# 00_PINOUT.net
KiCad netlist of a schematic drawn in Altium Designer
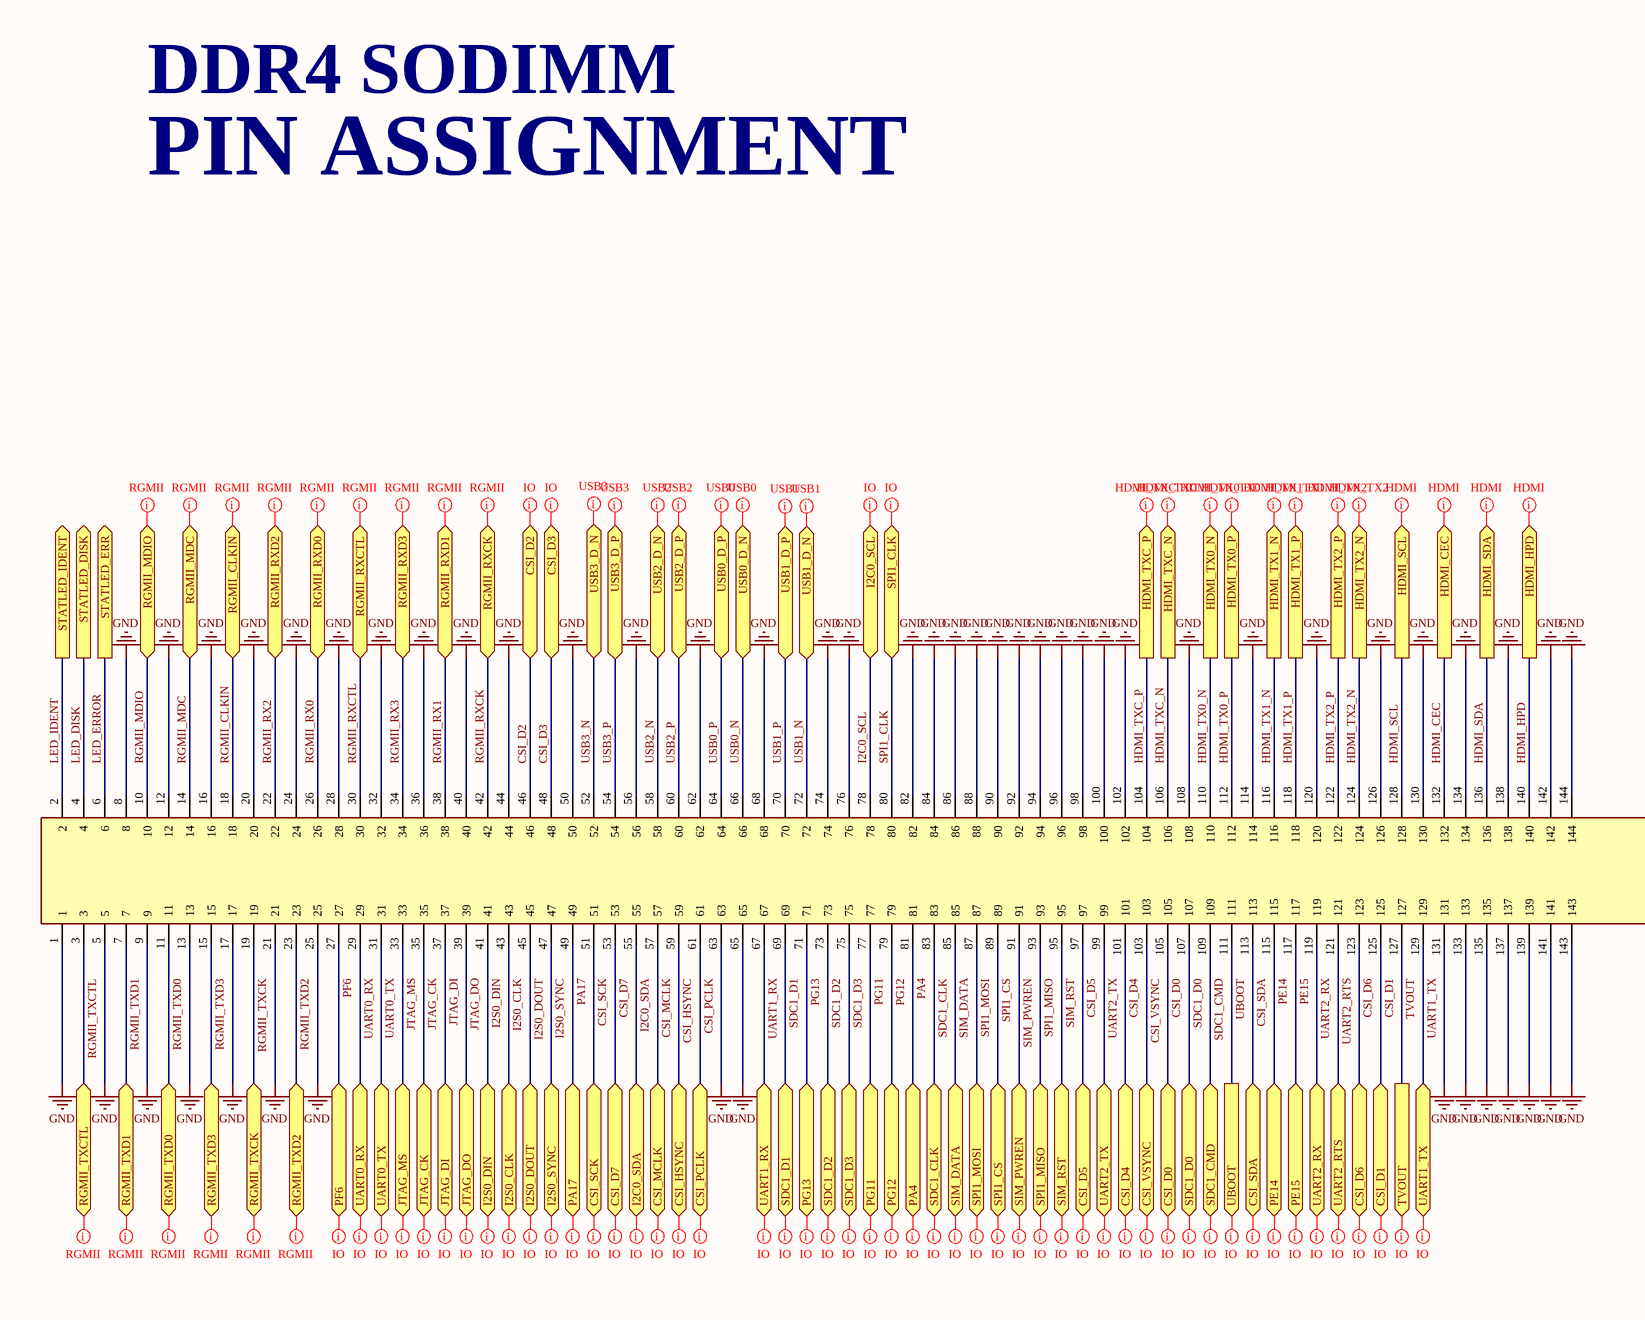
[diagram p0: 00_PINOUT.SchDoc, left]
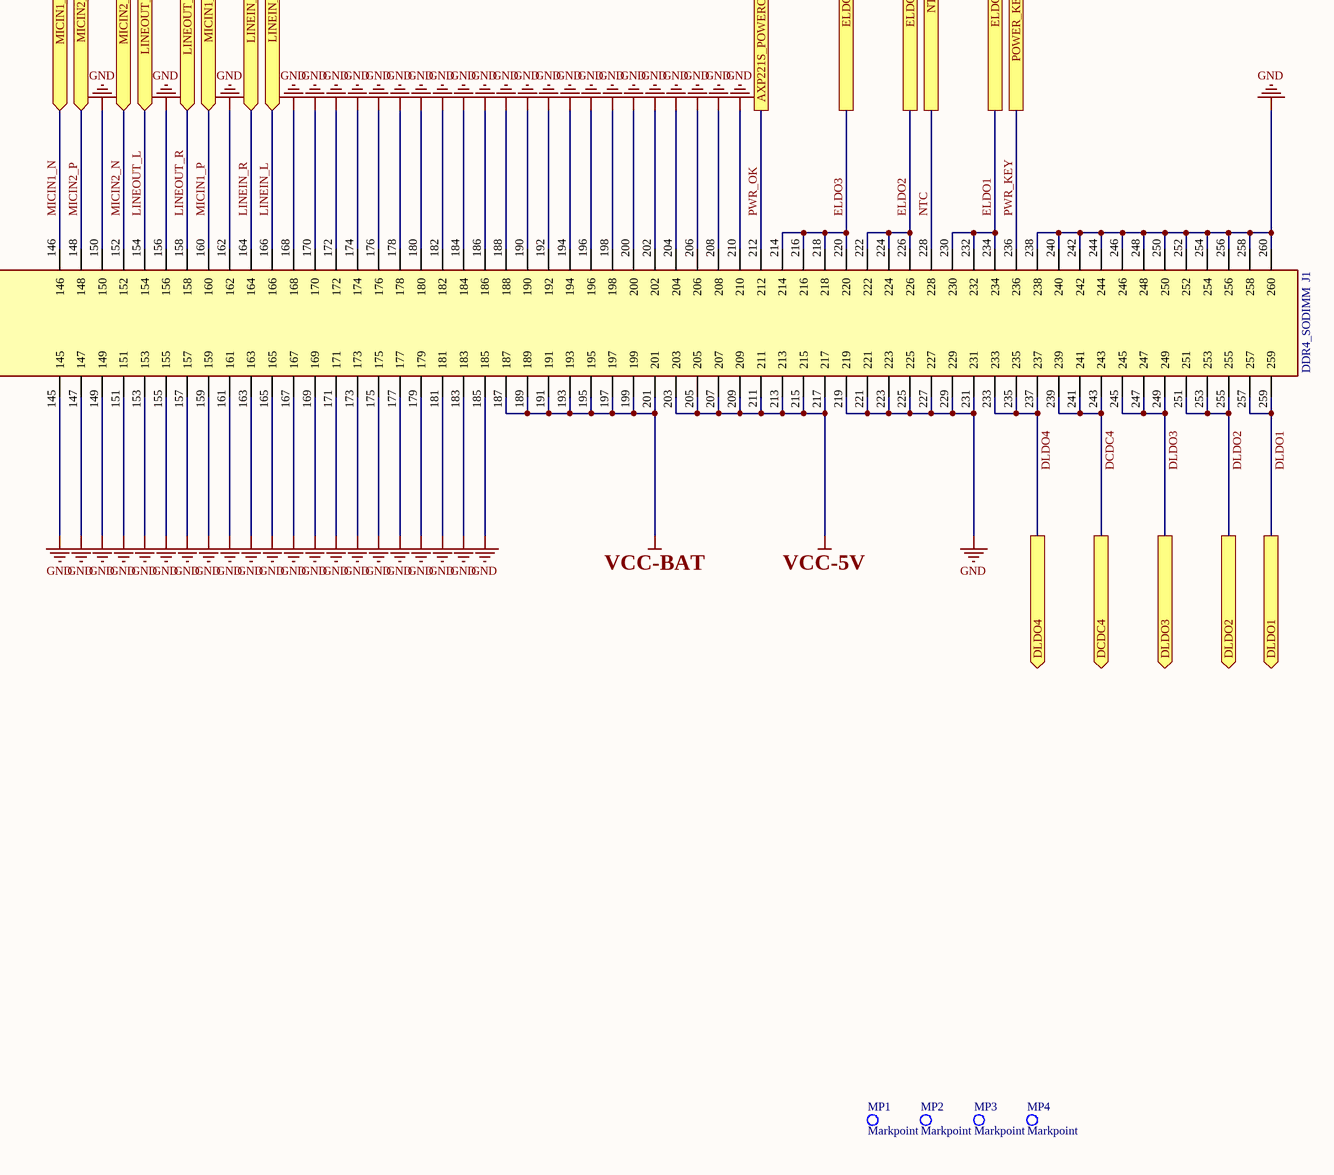
[diagram p1: 00_PINOUT.SchDoc, right]

(export (version "E")
  (design (tool "Eeschema 10.0.6"))
  (components
    (comp (ref "J1")
      (value "DDR4_SODIMM")
      (footprint "DDR4_SODIMM")
      (libsource (lib "Board") (part "DDR4_SODIMM"))
    )
    (comp (ref "MP1")
      (value "Markpoint")
      (footprint "MARKPOINT")
      (libsource (lib "Board") (part "MARKPOINT"))
    )
    (comp (ref "MP2")
      (value "Markpoint")
      (footprint "MARKPOINT")
      (libsource (lib "Board") (part "MARKPOINT"))
    )
    (comp (ref "MP3")
      (value "Markpoint")
      (footprint "MARKPOINT")
      (libsource (lib "Board") (part "MARKPOINT"))
    )
    (comp (ref "MP4")
      (value "Markpoint")
      (footprint "MARKPOINT")
      (libsource (lib "Board") (part "MARKPOINT"))
    )
  )
  (nets
    (net (code "1") (name "/CSI_D0") (class "Default")
      (node (ref "J1") (pin "105") (pinfunction "105_105") (pintype "passive"))
    )
    (net (code "2") (name "/CSI_D1") (class "Default")
      (node (ref "J1") (pin "125") (pinfunction "125_125") (pintype "passive"))
    )
    (net (code "3") (name "/CSI_D2") (class "Default")
      (node (ref "J1") (pin "46") (pinfunction "46_46") (pintype "passive"))
    )
    (net (code "4") (name "/CSI_D3") (class "Default")
      (node (ref "J1") (pin "48") (pinfunction "48_48") (pintype "passive"))
    )
    (net (code "5") (name "/CSI_D4") (class "Default")
      (node (ref "J1") (pin "101") (pinfunction "101_101") (pintype "passive"))
    )
    (net (code "6") (name "/CSI_D5") (class "Default")
      (node (ref "J1") (pin "97") (pinfunction "97_97") (pintype "passive"))
    )
    (net (code "7") (name "/CSI_D6") (class "Default")
      (node (ref "J1") (pin "123") (pinfunction "123_123") (pintype "passive"))
    )
    (net (code "8") (name "/CSI_D7") (class "Default")
      (node (ref "J1") (pin "53") (pinfunction "53_53") (pintype "passive"))
    )
    (net (code "9") (name "/CSI_HSYNC") (class "Default")
      (node (ref "J1") (pin "59") (pinfunction "59_59") (pintype "passive"))
    )
    (net (code "10") (name "/CSI_MCLK") (class "Default")
      (node (ref "J1") (pin "57") (pinfunction "57_57") (pintype "passive"))
    )
    (net (code "11") (name "/CSI_PCLK") (class "Default")
      (node (ref "J1") (pin "61") (pinfunction "61_61") (pintype "passive"))
    )
    (net (code "12") (name "/CSI_SCK") (class "Default")
      (node (ref "J1") (pin "51") (pinfunction "51_51") (pintype "passive"))
    )
    (net (code "13") (name "/CSI_SDA") (class "Default")
      (node (ref "J1") (pin "113") (pinfunction "113_113") (pintype "passive"))
    )
    (net (code "14") (name "/CSI_VSYNC") (class "Default")
      (node (ref "J1") (pin "103") (pinfunction "103_103") (pintype "passive"))
    )
    (net (code "15") (name "/DCDC4") (class "Default")
      (node (ref "J1") (pin "239") (pinfunction "239_239") (pintype "passive"))
      (node (ref "J1") (pin "241") (pinfunction "241_241") (pintype "passive"))
      (node (ref "J1") (pin "243") (pinfunction "243_243") (pintype "passive"))
    )
    (net (code "16") (name "/DLDO1") (class "Default")
      (node (ref "J1") (pin "257") (pinfunction "257_257") (pintype "passive"))
      (node (ref "J1") (pin "259") (pinfunction "259_259") (pintype "passive"))
    )
    (net (code "17") (name "/DLDO2") (class "Default")
      (node (ref "J1") (pin "251") (pinfunction "251_251") (pintype "passive"))
      (node (ref "J1") (pin "253") (pinfunction "253_253") (pintype "passive"))
      (node (ref "J1") (pin "255") (pinfunction "255_255") (pintype "passive"))
    )
    (net (code "18") (name "/DLDO3") (class "Default")
      (node (ref "J1") (pin "245") (pinfunction "245_245") (pintype "passive"))
      (node (ref "J1") (pin "247") (pinfunction "247_247") (pintype "passive"))
      (node (ref "J1") (pin "249") (pinfunction "249_249") (pintype "passive"))
    )
    (net (code "19") (name "/DLDO4") (class "Default")
      (node (ref "J1") (pin "233") (pinfunction "233_233") (pintype "passive"))
      (node (ref "J1") (pin "235") (pinfunction "235_235") (pintype "passive"))
      (node (ref "J1") (pin "237") (pinfunction "237_237") (pintype "passive"))
    )
    (net (code "20") (name "/ELDO1") (class "Default")
      (node (ref "J1") (pin "230") (pinfunction "230_230") (pintype "passive"))
      (node (ref "J1") (pin "232") (pinfunction "232_232") (pintype "passive"))
      (node (ref "J1") (pin "234") (pinfunction "234_234") (pintype "passive"))
    )
    (net (code "21") (name "/ELDO2") (class "Default")
      (node (ref "J1") (pin "222") (pinfunction "222_222") (pintype "passive"))
      (node (ref "J1") (pin "224") (pinfunction "224_224") (pintype "passive"))
      (node (ref "J1") (pin "226") (pinfunction "226_226") (pintype "passive"))
    )
    (net (code "22") (name "/ELDO3") (class "Default")
      (node (ref "J1") (pin "214") (pinfunction "214_214") (pintype "passive"))
      (node (ref "J1") (pin "216") (pinfunction "216_216") (pintype "passive"))
      (node (ref "J1") (pin "218") (pinfunction "218_218") (pintype "passive"))
      (node (ref "J1") (pin "220") (pinfunction "220_220") (pintype "passive"))
    )
    (net (code "23") (name "/HDMI_CEC") (class "Default")
      (node (ref "J1") (pin "132") (pinfunction "132_132") (pintype "passive"))
    )
    (net (code "24") (name "/HDMI_HPD") (class "Default")
      (node (ref "J1") (pin "140") (pinfunction "140_140") (pintype "passive"))
    )
    (net (code "25") (name "/HDMI_SCL") (class "Default")
      (node (ref "J1") (pin "128") (pinfunction "128_128") (pintype "passive"))
    )
    (net (code "26") (name "/HDMI_SDA") (class "Default")
      (node (ref "J1") (pin "136") (pinfunction "136_136") (pintype "passive"))
    )
    (net (code "27") (name "/HDMI_TX0_N") (class "Default")
      (node (ref "J1") (pin "110") (pinfunction "110_110") (pintype "passive"))
    )
    (net (code "28") (name "/HDMI_TX0_P") (class "Default")
      (node (ref "J1") (pin "112") (pinfunction "112_112") (pintype "passive"))
    )
    (net (code "29") (name "/HDMI_TX1_N") (class "Default")
      (node (ref "J1") (pin "116") (pinfunction "116_116") (pintype "passive"))
    )
    (net (code "30") (name "/HDMI_TX1_P") (class "Default")
      (node (ref "J1") (pin "118") (pinfunction "118_118") (pintype "passive"))
    )
    (net (code "31") (name "/HDMI_TX2_N") (class "Default")
      (node (ref "J1") (pin "124") (pinfunction "124_124") (pintype "passive"))
    )
    (net (code "32") (name "/HDMI_TX2_P") (class "Default")
      (node (ref "J1") (pin "122") (pinfunction "122_122") (pintype "passive"))
    )
    (net (code "33") (name "/HDMI_TXC_N") (class "Default")
      (node (ref "J1") (pin "106") (pinfunction "106_106") (pintype "passive"))
    )
    (net (code "34") (name "/HDMI_TXC_P") (class "Default")
      (node (ref "J1") (pin "104") (pinfunction "104_104") (pintype "passive"))
    )
    (net (code "35") (name "/I2C0_SCL") (class "Default")
      (node (ref "J1") (pin "78") (pinfunction "78_78") (pintype "passive"))
    )
    (net (code "36") (name "/I2C0_SDA") (class "Default")
      (node (ref "J1") (pin "55") (pinfunction "55_55") (pintype "passive"))
    )
    (net (code "37") (name "/I2S0_CLK") (class "Default")
      (node (ref "J1") (pin "43") (pinfunction "43_43") (pintype "passive"))
    )
    (net (code "38") (name "/I2S0_DIN") (class "Default")
      (node (ref "J1") (pin "41") (pinfunction "41_41") (pintype "passive"))
    )
    (net (code "39") (name "/I2S0_DOUT") (class "Default")
      (node (ref "J1") (pin "45") (pinfunction "45_45") (pintype "passive"))
    )
    (net (code "40") (name "/I2S0_SYNC") (class "Default")
      (node (ref "J1") (pin "47") (pinfunction "47_47") (pintype "passive"))
    )
    (net (code "41") (name "/JTAG_CK") (class "Default")
      (node (ref "J1") (pin "35") (pinfunction "35_35") (pintype "passive"))
    )
    (net (code "42") (name "/JTAG_DI") (class "Default")
      (node (ref "J1") (pin "37") (pinfunction "37_37") (pintype "passive"))
    )
    (net (code "43") (name "/JTAG_DO") (class "Default")
      (node (ref "J1") (pin "39") (pinfunction "39_39") (pintype "passive"))
    )
    (net (code "44") (name "/JTAG_MS") (class "Default")
      (node (ref "J1") (pin "33") (pinfunction "33_33") (pintype "passive"))
    )
    (net (code "45") (name "/LED_DISK") (class "Default")
      (node (ref "J1") (pin "4") (pinfunction "4_4") (pintype "passive"))
    )
    (net (code "46") (name "/LED_ERROR") (class "Default")
      (node (ref "J1") (pin "6") (pinfunction "6_6") (pintype "passive"))
    )
    (net (code "47") (name "/LED_IDENT") (class "Default")
      (node (ref "J1") (pin "2") (pinfunction "2_2") (pintype "passive"))
    )
    (net (code "48") (name "/LINEIN_L") (class "Default")
      (node (ref "J1") (pin "166") (pinfunction "166_166") (pintype "passive"))
    )
    (net (code "49") (name "/LINEIN_R") (class "Default")
      (node (ref "J1") (pin "164") (pinfunction "164_164") (pintype "passive"))
    )
    (net (code "50") (name "/LINEOUT_L") (class "Default")
      (node (ref "J1") (pin "154") (pinfunction "154_154") (pintype "passive"))
    )
    (net (code "51") (name "/LINEOUT_R") (class "Default")
      (node (ref "J1") (pin "158") (pinfunction "158_158") (pintype "passive"))
    )
    (net (code "52") (name "/MICIN1_N") (class "Default")
      (node (ref "J1") (pin "146") (pinfunction "146_146") (pintype "passive"))
    )
    (net (code "53") (name "/MICIN1_P") (class "Default")
      (node (ref "J1") (pin "160") (pinfunction "160_160") (pintype "passive"))
    )
    (net (code "54") (name "/MICIN2_N") (class "Default")
      (node (ref "J1") (pin "152") (pinfunction "152_152") (pintype "passive"))
    )
    (net (code "55") (name "/MICIN2_P") (class "Default")
      (node (ref "J1") (pin "148") (pinfunction "148_148") (pintype "passive"))
    )
    (net (code "56") (name "/NTC") (class "Default")
      (node (ref "J1") (pin "228") (pinfunction "228_228") (pintype "passive"))
    )
    (net (code "57") (name "/PA4") (class "Default")
      (node (ref "J1") (pin "81") (pinfunction "81_81") (pintype "passive"))
    )
    (net (code "58") (name "/PA17") (class "Default")
      (node (ref "J1") (pin "49") (pinfunction "49_49") (pintype "passive"))
    )
    (net (code "59") (name "/PE14") (class "Default")
      (node (ref "J1") (pin "115") (pinfunction "115_115") (pintype "passive"))
    )
    (net (code "60") (name "/PE15") (class "Default")
      (node (ref "J1") (pin "117") (pinfunction "117_117") (pintype "passive"))
    )
    (net (code "61") (name "/PF6") (class "Default")
      (node (ref "J1") (pin "27") (pinfunction "27_27") (pintype "passive"))
    )
    (net (code "62") (name "/PG11") (class "Default")
      (node (ref "J1") (pin "77") (pinfunction "77_77") (pintype "passive"))
    )
    (net (code "63") (name "/PG12") (class "Default")
      (node (ref "J1") (pin "79") (pinfunction "79_79") (pintype "passive"))
    )
    (net (code "64") (name "/PG13") (class "Default")
      (node (ref "J1") (pin "71") (pinfunction "71_71") (pintype "passive"))
    )
    (net (code "65") (name "/PWR_KEY") (class "Default")
      (node (ref "J1") (pin "236") (pinfunction "236_236") (pintype "passive"))
    )
    (net (code "66") (name "/PWR_OK") (class "Default")
      (node (ref "J1") (pin "212") (pinfunction "212_212") (pintype "passive"))
    )
    (net (code "67") (name "/RGMII_CLKIN") (class "Default")
      (node (ref "J1") (pin "18") (pinfunction "18_18") (pintype "passive"))
    )
    (net (code "68") (name "/RGMII_MDC") (class "Default")
      (node (ref "J1") (pin "14") (pinfunction "14_14") (pintype "passive"))
    )
    (net (code "69") (name "/RGMII_MDIO") (class "Default")
      (node (ref "J1") (pin "10") (pinfunction "10_10") (pintype "passive"))
    )
    (net (code "70") (name "/RGMII_RX0") (class "Default")
      (node (ref "J1") (pin "26") (pinfunction "26_26") (pintype "passive"))
    )
    (net (code "71") (name "/RGMII_RX1") (class "Default")
      (node (ref "J1") (pin "38") (pinfunction "38_38") (pintype "passive"))
    )
    (net (code "72") (name "/RGMII_RX2") (class "Default")
      (node (ref "J1") (pin "22") (pinfunction "22_22") (pintype "passive"))
    )
    (net (code "73") (name "/RGMII_RX3") (class "Default")
      (node (ref "J1") (pin "34") (pinfunction "34_34") (pintype "passive"))
    )
    (net (code "74") (name "/RGMII_RXCK") (class "Default")
      (node (ref "J1") (pin "42") (pinfunction "42_42") (pintype "passive"))
    )
    (net (code "75") (name "/RGMII_RXCTL") (class "Default")
      (node (ref "J1") (pin "30") (pinfunction "30_30") (pintype "passive"))
    )
    (net (code "76") (name "/RGMII_TXCK") (class "Default")
      (node (ref "J1") (pin "19") (pinfunction "19_19") (pintype "passive"))
    )
    (net (code "77") (name "/RGMII_TXCTL") (class "Default")
      (node (ref "J1") (pin "3") (pinfunction "3_3") (pintype "passive"))
    )
    (net (code "78") (name "/RGMII_TXD0") (class "Default")
      (node (ref "J1") (pin "11") (pinfunction "11_11") (pintype "passive"))
    )
    (net (code "79") (name "/RGMII_TXD1") (class "Default")
      (node (ref "J1") (pin "7") (pinfunction "7_7") (pintype "passive"))
    )
    (net (code "80") (name "/RGMII_TXD2") (class "Default")
      (node (ref "J1") (pin "23") (pinfunction "23_23") (pintype "passive"))
    )
    (net (code "81") (name "/RGMII_TXD3") (class "Default")
      (node (ref "J1") (pin "15") (pinfunction "15_15") (pintype "passive"))
    )
    (net (code "82") (name "/SDC1_CLK") (class "Default")
      (node (ref "J1") (pin "83") (pinfunction "83_83") (pintype "passive"))
    )
    (net (code "83") (name "/SDC1_CMD") (class "Default")
      (node (ref "J1") (pin "109") (pinfunction "109_109") (pintype "passive"))
    )
    (net (code "84") (name "/SDC1_D0") (class "Default")
      (node (ref "J1") (pin "107") (pinfunction "107_107") (pintype "passive"))
    )
    (net (code "85") (name "/SDC1_D1") (class "Default")
      (node (ref "J1") (pin "69") (pinfunction "69_69") (pintype "passive"))
    )
    (net (code "86") (name "/SDC1_D2") (class "Default")
      (node (ref "J1") (pin "73") (pinfunction "73_73") (pintype "passive"))
    )
    (net (code "87") (name "/SDC1_D3") (class "Default")
      (node (ref "J1") (pin "75") (pinfunction "75_75") (pintype "passive"))
    )
    (net (code "88") (name "/SIM_DATA") (class "Default")
      (node (ref "J1") (pin "85") (pinfunction "85_85") (pintype "passive"))
    )
    (net (code "89") (name "/SIM_PWREN") (class "Default")
      (node (ref "J1") (pin "91") (pinfunction "91_91") (pintype "passive"))
    )
    (net (code "90") (name "/SIM_RST") (class "Default")
      (node (ref "J1") (pin "95") (pinfunction "95_95") (pintype "passive"))
    )
    (net (code "91") (name "/SPI1_CLK") (class "Default")
      (node (ref "J1") (pin "80") (pinfunction "80_80") (pintype "passive"))
    )
    (net (code "92") (name "/SPI1_CS") (class "Default")
      (node (ref "J1") (pin "89") (pinfunction "89_89") (pintype "passive"))
    )
    (net (code "93") (name "/SPI1_MISO") (class "Default")
      (node (ref "J1") (pin "93") (pinfunction "93_93") (pintype "passive"))
    )
    (net (code "94") (name "/SPI1_MOSI") (class "Default")
      (node (ref "J1") (pin "87") (pinfunction "87_87") (pintype "passive"))
    )
    (net (code "95") (name "/TVOUT") (class "Default")
      (node (ref "J1") (pin "127") (pinfunction "127_127") (pintype "passive"))
    )
    (net (code "96") (name "/UART0_RX") (class "Default")
      (node (ref "J1") (pin "29") (pinfunction "29_29") (pintype "passive"))
    )
    (net (code "97") (name "/UART0_TX") (class "Default")
      (node (ref "J1") (pin "31") (pinfunction "31_31") (pintype "passive"))
    )
    (net (code "98") (name "/UART1_RX") (class "Default")
      (node (ref "J1") (pin "67") (pinfunction "67_67") (pintype "passive"))
    )
    (net (code "99") (name "/UART1_TX") (class "Default")
      (node (ref "J1") (pin "129") (pinfunction "129_129") (pintype "passive"))
    )
    (net (code "100") (name "/UART2_RTS") (class "Default")
      (node (ref "J1") (pin "121") (pinfunction "121_121") (pintype "passive"))
    )
    (net (code "101") (name "/UART2_RX") (class "Default")
      (node (ref "J1") (pin "119") (pinfunction "119_119") (pintype "passive"))
    )
    (net (code "102") (name "/UART2_TX") (class "Default")
      (node (ref "J1") (pin "99") (pinfunction "99_99") (pintype "passive"))
    )
    (net (code "103") (name "/UBOOT") (class "Default")
      (node (ref "J1") (pin "111") (pinfunction "111_111") (pintype "passive"))
    )
    (net (code "104") (name "/USB0_N") (class "Default")
      (node (ref "J1") (pin "66") (pinfunction "66_66") (pintype "passive"))
    )
    (net (code "105") (name "/USB0_P") (class "Default")
      (node (ref "J1") (pin "64") (pinfunction "64_64") (pintype "passive"))
    )
    (net (code "106") (name "/USB1_N") (class "Default")
      (node (ref "J1") (pin "72") (pinfunction "72_72") (pintype "passive"))
    )
    (net (code "107") (name "/USB1_P") (class "Default")
      (node (ref "J1") (pin "70") (pinfunction "70_70") (pintype "passive"))
    )
    (net (code "108") (name "/USB2_N") (class "Default")
      (node (ref "J1") (pin "58") (pinfunction "58_58") (pintype "passive"))
    )
    (net (code "109") (name "/USB2_P") (class "Default")
      (node (ref "J1") (pin "60") (pinfunction "60_60") (pintype "passive"))
    )
    (net (code "110") (name "/USB3_N") (class "Default")
      (node (ref "J1") (pin "52") (pinfunction "52_52") (pintype "passive"))
    )
    (net (code "111") (name "/USB3_P") (class "Default")
      (node (ref "J1") (pin "54") (pinfunction "54_54") (pintype "passive"))
    )
    (net (code "112") (name "GND") (class "Default")
      (node (ref "J1") (pin "1") (pinfunction "1_1") (pintype "passive"))
      (node (ref "J1") (pin "100") (pinfunction "100_100") (pintype "passive"))
      (node (ref "J1") (pin "102") (pinfunction "102_102") (pintype "passive"))
      (node (ref "J1") (pin "108") (pinfunction "108_108") (pintype "passive"))
      (node (ref "J1") (pin "114") (pinfunction "114_114") (pintype "passive"))
      (node (ref "J1") (pin "12") (pinfunction "12_12") (pintype "passive"))
      (node (ref "J1") (pin "120") (pinfunction "120_120") (pintype "passive"))
      (node (ref "J1") (pin "126") (pinfunction "126_126") (pintype "passive"))
      (node (ref "J1") (pin "13") (pinfunction "13_13") (pintype "passive"))
      (node (ref "J1") (pin "130") (pinfunction "130_130") (pintype "passive"))
      (node (ref "J1") (pin "131") (pinfunction "131_131") (pintype "passive"))
      (node (ref "J1") (pin "133") (pinfunction "133_133") (pintype "passive"))
      (node (ref "J1") (pin "134") (pinfunction "134_134") (pintype "passive"))
      (node (ref "J1") (pin "135") (pinfunction "135_135") (pintype "passive"))
      (node (ref "J1") (pin "137") (pinfunction "137_137") (pintype "passive"))
      (node (ref "J1") (pin "138") (pinfunction "138_138") (pintype "passive"))
      (node (ref "J1") (pin "139") (pinfunction "139_139") (pintype "passive"))
      (node (ref "J1") (pin "141") (pinfunction "141_141") (pintype "passive"))
      (node (ref "J1") (pin "142") (pinfunction "142_142") (pintype "passive"))
      (node (ref "J1") (pin "143") (pinfunction "143_143") (pintype "passive"))
      (node (ref "J1") (pin "144") (pinfunction "144_144") (pintype "passive"))
      (node (ref "J1") (pin "145") (pinfunction "145_145") (pintype "passive"))
      (node (ref "J1") (pin "147") (pinfunction "147_147") (pintype "passive"))
      (node (ref "J1") (pin "149") (pinfunction "149_149") (pintype "passive"))
      (node (ref "J1") (pin "150") (pinfunction "150_150") (pintype "passive"))
      (node (ref "J1") (pin "151") (pinfunction "151_151") (pintype "passive"))
      (node (ref "J1") (pin "153") (pinfunction "153_153") (pintype "passive"))
      (node (ref "J1") (pin "155") (pinfunction "155_155") (pintype "passive"))
      (node (ref "J1") (pin "156") (pinfunction "156_156") (pintype "passive"))
      (node (ref "J1") (pin "157") (pinfunction "157_157") (pintype "passive"))
      (node (ref "J1") (pin "159") (pinfunction "159_159") (pintype "passive"))
      (node (ref "J1") (pin "16") (pinfunction "16_16") (pintype "passive"))
      (node (ref "J1") (pin "161") (pinfunction "161_161") (pintype "passive"))
      (node (ref "J1") (pin "162") (pinfunction "162_162") (pintype "passive"))
      (node (ref "J1") (pin "163") (pinfunction "163_163") (pintype "passive"))
      (node (ref "J1") (pin "165") (pinfunction "165_165") (pintype "passive"))
      (node (ref "J1") (pin "167") (pinfunction "167_167") (pintype "passive"))
      (node (ref "J1") (pin "168") (pinfunction "168_168") (pintype "passive"))
      (node (ref "J1") (pin "169") (pinfunction "169_169") (pintype "passive"))
      (node (ref "J1") (pin "17") (pinfunction "17_17") (pintype "passive"))
      (node (ref "J1") (pin "170") (pinfunction "170_170") (pintype "passive"))
      (node (ref "J1") (pin "171") (pinfunction "171_171") (pintype "passive"))
      (node (ref "J1") (pin "172") (pinfunction "172_172") (pintype "passive"))
      (node (ref "J1") (pin "173") (pinfunction "173_173") (pintype "passive"))
      (node (ref "J1") (pin "174") (pinfunction "174_174") (pintype "passive"))
      (node (ref "J1") (pin "175") (pinfunction "175_175") (pintype "passive"))
      (node (ref "J1") (pin "176") (pinfunction "176_176") (pintype "passive"))
      (node (ref "J1") (pin "177") (pinfunction "177_177") (pintype "passive"))
      (node (ref "J1") (pin "178") (pinfunction "178_178") (pintype "passive"))
      (node (ref "J1") (pin "179") (pinfunction "179_179") (pintype "passive"))
      (node (ref "J1") (pin "180") (pinfunction "180_180") (pintype "passive"))
      (node (ref "J1") (pin "181") (pinfunction "181_181") (pintype "passive"))
      (node (ref "J1") (pin "182") (pinfunction "182_182") (pintype "passive"))
      (node (ref "J1") (pin "183") (pinfunction "183_183") (pintype "passive"))
      (node (ref "J1") (pin "184") (pinfunction "184_184") (pintype "passive"))
      (node (ref "J1") (pin "185") (pinfunction "185_185") (pintype "passive"))
      (node (ref "J1") (pin "186") (pinfunction "186_186") (pintype "passive"))
      (node (ref "J1") (pin "188") (pinfunction "188_188") (pintype "passive"))
      (node (ref "J1") (pin "190") (pinfunction "190_190") (pintype "passive"))
      (node (ref "J1") (pin "192") (pinfunction "192_192") (pintype "passive"))
      (node (ref "J1") (pin "194") (pinfunction "194_194") (pintype "passive"))
      (node (ref "J1") (pin "196") (pinfunction "196_196") (pintype "passive"))
      (node (ref "J1") (pin "198") (pinfunction "198_198") (pintype "passive"))
      (node (ref "J1") (pin "20") (pinfunction "20_20") (pintype "passive"))
      (node (ref "J1") (pin "200") (pinfunction "200_200") (pintype "passive"))
      (node (ref "J1") (pin "202") (pinfunction "202_202") (pintype "passive"))
      (node (ref "J1") (pin "204") (pinfunction "204_204") (pintype "passive"))
      (node (ref "J1") (pin "206") (pinfunction "206_206") (pintype "passive"))
      (node (ref "J1") (pin "208") (pinfunction "208_208") (pintype "passive"))
      (node (ref "J1") (pin "21") (pinfunction "21_21") (pintype "passive"))
      (node (ref "J1") (pin "210") (pinfunction "210_210") (pintype "passive"))
      (node (ref "J1") (pin "219") (pinfunction "219_219") (pintype "passive"))
      (node (ref "J1") (pin "221") (pinfunction "221_221") (pintype "passive"))
      (node (ref "J1") (pin "223") (pinfunction "223_223") (pintype "passive"))
      (node (ref "J1") (pin "225") (pinfunction "225_225") (pintype "passive"))
      (node (ref "J1") (pin "227") (pinfunction "227_227") (pintype "passive"))
      (node (ref "J1") (pin "229") (pinfunction "229_229") (pintype "passive"))
      (node (ref "J1") (pin "231") (pinfunction "231_231") (pintype "passive"))
      (node (ref "J1") (pin "238") (pinfunction "238_238") (pintype "passive"))
      (node (ref "J1") (pin "24") (pinfunction "24_24") (pintype "passive"))
      (node (ref "J1") (pin "240") (pinfunction "240_240") (pintype "passive"))
      (node (ref "J1") (pin "242") (pinfunction "242_242") (pintype "passive"))
      (node (ref "J1") (pin "244") (pinfunction "244_244") (pintype "passive"))
      (node (ref "J1") (pin "246") (pinfunction "246_246") (pintype "passive"))
      (node (ref "J1") (pin "248") (pinfunction "248_248") (pintype "passive"))
      (node (ref "J1") (pin "25") (pinfunction "25_25") (pintype "passive"))
      (node (ref "J1") (pin "250") (pinfunction "250_250") (pintype "passive"))
      (node (ref "J1") (pin "252") (pinfunction "252_252") (pintype "passive"))
      (node (ref "J1") (pin "254") (pinfunction "254_254") (pintype "passive"))
      (node (ref "J1") (pin "256") (pinfunction "256_256") (pintype "passive"))
      (node (ref "J1") (pin "258") (pinfunction "258_258") (pintype "passive"))
      (node (ref "J1") (pin "260") (pinfunction "260_260") (pintype "passive"))
      (node (ref "J1") (pin "28") (pinfunction "28_28") (pintype "passive"))
      (node (ref "J1") (pin "32") (pinfunction "32_32") (pintype "passive"))
      (node (ref "J1") (pin "36") (pinfunction "36_36") (pintype "passive"))
      (node (ref "J1") (pin "40") (pinfunction "40_40") (pintype "passive"))
      (node (ref "J1") (pin "44") (pinfunction "44_44") (pintype "passive"))
      (node (ref "J1") (pin "5") (pinfunction "5_5") (pintype "passive"))
      (node (ref "J1") (pin "50") (pinfunction "50_50") (pintype "passive"))
      (node (ref "J1") (pin "56") (pinfunction "56_56") (pintype "passive"))
      (node (ref "J1") (pin "62") (pinfunction "62_62") (pintype "passive"))
      (node (ref "J1") (pin "63") (pinfunction "63_63") (pintype "passive"))
      (node (ref "J1") (pin "65") (pinfunction "65_65") (pintype "passive"))
      (node (ref "J1") (pin "68") (pinfunction "68_68") (pintype "passive"))
      (node (ref "J1") (pin "74") (pinfunction "74_74") (pintype "passive"))
      (node (ref "J1") (pin "76") (pinfunction "76_76") (pintype "passive"))
      (node (ref "J1") (pin "8") (pinfunction "8_8") (pintype "passive"))
      (node (ref "J1") (pin "82") (pinfunction "82_82") (pintype "passive"))
      (node (ref "J1") (pin "84") (pinfunction "84_84") (pintype "passive"))
      (node (ref "J1") (pin "86") (pinfunction "86_86") (pintype "passive"))
      (node (ref "J1") (pin "88") (pinfunction "88_88") (pintype "passive"))
      (node (ref "J1") (pin "9") (pinfunction "9_9") (pintype "passive"))
      (node (ref "J1") (pin "90") (pinfunction "90_90") (pintype "passive"))
      (node (ref "J1") (pin "92") (pinfunction "92_92") (pintype "passive"))
      (node (ref "J1") (pin "94") (pinfunction "94_94") (pintype "passive"))
      (node (ref "J1") (pin "96") (pinfunction "96_96") (pintype "passive"))
      (node (ref "J1") (pin "98") (pinfunction "98_98") (pintype "passive"))
    )
    (net (code "113") (name "VCC-5V") (class "Default")
      (node (ref "J1") (pin "203") (pinfunction "203_203") (pintype "passive"))
      (node (ref "J1") (pin "205") (pinfunction "205_205") (pintype "passive"))
      (node (ref "J1") (pin "207") (pinfunction "207_207") (pintype "passive"))
      (node (ref "J1") (pin "209") (pinfunction "209_209") (pintype "passive"))
      (node (ref "J1") (pin "211") (pinfunction "211_211") (pintype "passive"))
      (node (ref "J1") (pin "213") (pinfunction "213_213") (pintype "passive"))
      (node (ref "J1") (pin "215") (pinfunction "215_215") (pintype "passive"))
      (node (ref "J1") (pin "217") (pinfunction "217_217") (pintype "passive"))
    )
    (net (code "114") (name "VCC-BAT") (class "Default")
      (node (ref "J1") (pin "187") (pinfunction "187_187") (pintype "passive"))
      (node (ref "J1") (pin "189") (pinfunction "189_189") (pintype "passive"))
      (node (ref "J1") (pin "191") (pinfunction "191_191") (pintype "passive"))
      (node (ref "J1") (pin "193") (pinfunction "193_193") (pintype "passive"))
      (node (ref "J1") (pin "195") (pinfunction "195_195") (pintype "passive"))
      (node (ref "J1") (pin "197") (pinfunction "197_197") (pintype "passive"))
      (node (ref "J1") (pin "199") (pinfunction "199_199") (pintype "passive"))
      (node (ref "J1") (pin "201") (pinfunction "201_201") (pintype "passive"))
    )
  )
)
